# RMII_Ethernet.net
KiCad netlist of a schematic drawn in Altium Designer
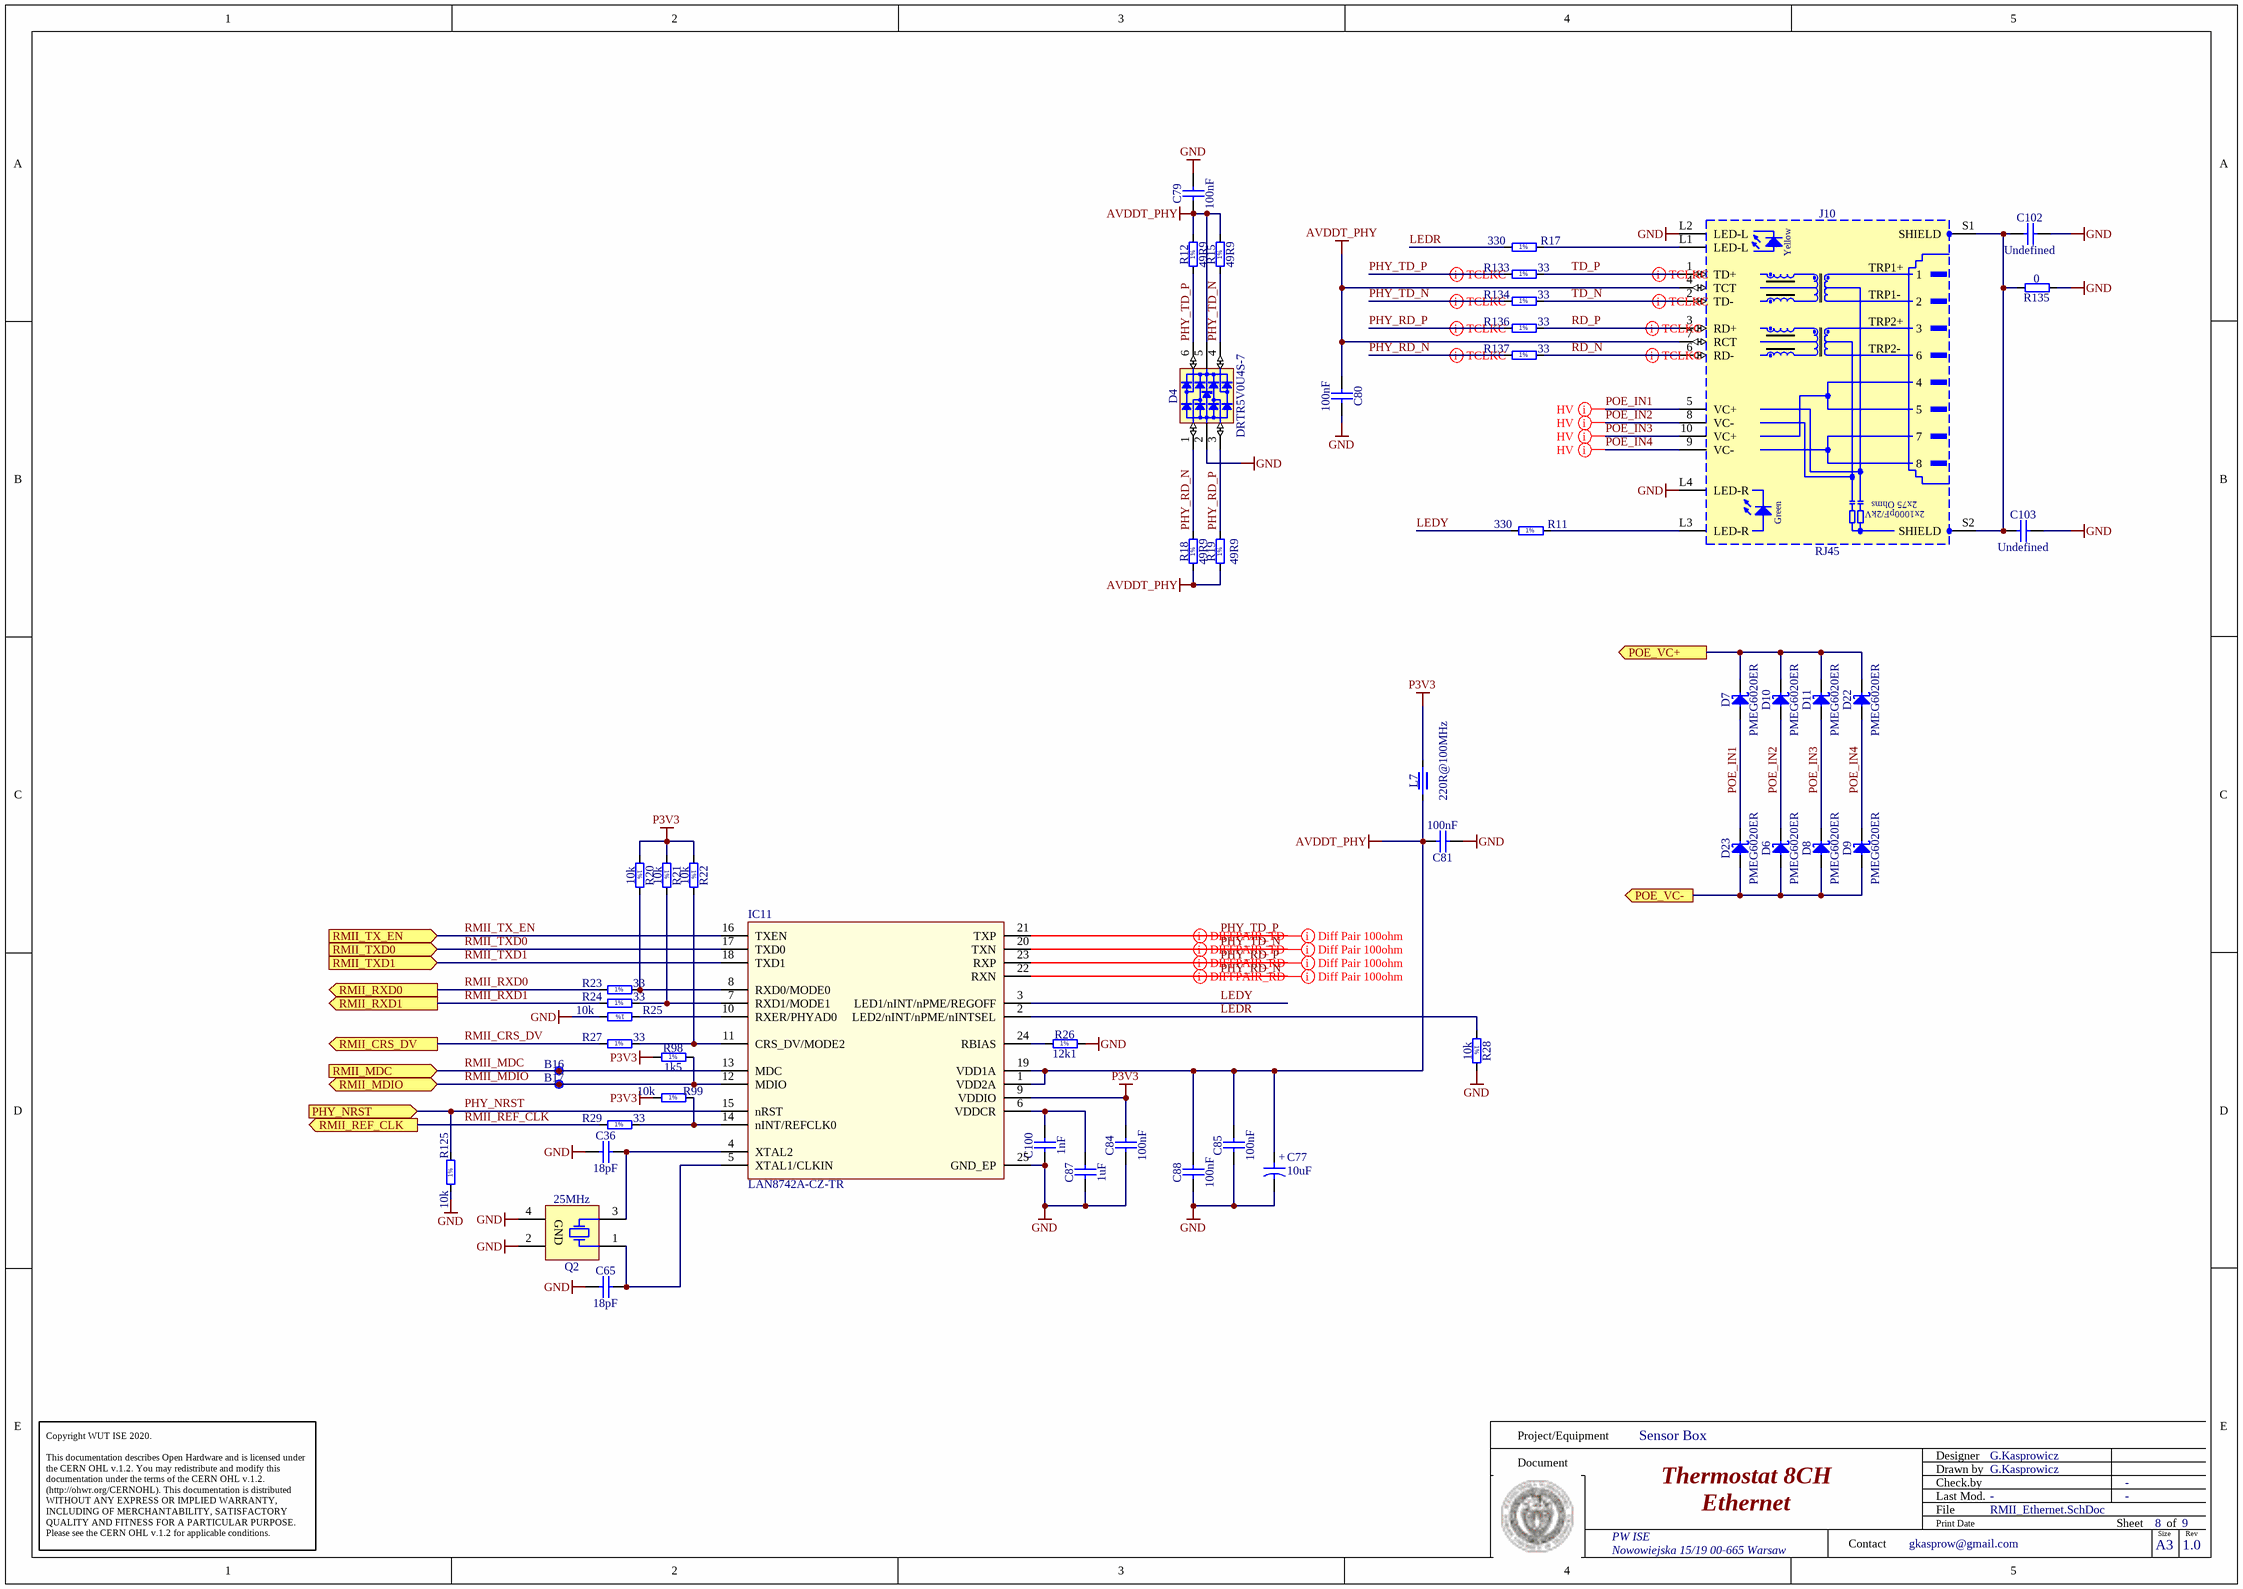
[diagram p0: RMII_Ethernet.SchDoc]

(export (version "E")
  (design (tool "Eeschema 10.0.6"))
  (components
    (comp (ref "B16")
      (value "SMD Pad")
      (footprint "C100")
      (description "Through Hole Pad")
      (fields (field (name "PART NUMBER") "SMD_PAD_D1MM") (field (name "AUTHOR") "CERN DEM JLC"))
      (libsource (lib "Eletro-mechanical") (part "Single SMD Pad (Round)"))
    )
    (comp (ref "B17")
      (value "SMD Pad")
      (footprint "C100")
      (description "Through Hole Pad")
      (fields (field (name "PART NUMBER") "SMD_PAD_D1MM") (field (name "AUTHOR") "CERN DEM JLC"))
      (libsource (lib "Eletro-mechanical") (part "Single SMD Pad (Round)"))
    )
    (comp (ref "C36")
      (value "18pF")
      (footprint "CAPC1005X55N")
      (description "Non-polarised capacitor")
      (fields
        (field (name "PART NUMBER") "CC0402_18PF_50V_5%_C0G")
        (field (name "VOLTAGE") "50V")
        (field (name "AUTHOR") "CERN DEM JLC")
      )
      (libsource (lib "Capacitors") (part "Capacitor - non polarized"))
    )
    (comp (ref "C65")
      (value "18pF")
      (footprint "CAPC1005X55N")
      (description "Non-polarised capacitor")
      (fields
        (field (name "PART NUMBER") "CC0402_18PF_50V_5%_C0G")
        (field (name "VOLTAGE") "50V")
        (field (name "AUTHOR") "CERN DEM JLC")
      )
      (libsource (lib "Capacitors") (part "Capacitor - non polarized"))
    )
    (comp (ref "C77")
      (value "10uF")
      (footprint "CAPMP3216X180N")
      (description "Polarised capacitor")
      (fields
        (field (name "PART NUMBER") "CTE3216-18_10UF_16V_20%_AVX_TCJ")
        (field (name "VOLTAGE") "16V")
        (field (name "AUTHOR") "CERN DEM JLC")
      )
      (libsource (lib "Capacitors") (part "Capacitor - polarized"))
    )
    (comp (ref "C79")
      (value "100nF")
      (footprint "CAPC1005X55N")
      (description "Non-polarised capacitor")
      (fields
        (field (name "PART NUMBER") "CC0402_100NF_16V_10%_X5R")
        (field (name "VOLTAGE") "16V")
        (field (name "AUTHOR") "CERN DEM JLC")
      )
      (libsource (lib "Capacitors") (part "Capacitor - non polarized"))
    )
    (comp (ref "C80")
      (value "100nF")
      (footprint "CAPC1005X55N")
      (description "Non-polarised capacitor")
      (fields
        (field (name "PART NUMBER") "CC0402_100NF_16V_10%_X5R")
        (field (name "VOLTAGE") "16V")
        (field (name "AUTHOR") "CERN DEM JLC")
      )
      (libsource (lib "Capacitors") (part "Capacitor - non polarized"))
    )
    (comp (ref "C81")
      (value "100nF")
      (footprint "CAPC1005X55N")
      (description "Non-polarised capacitor")
      (fields
        (field (name "PART NUMBER") "CC0402_100NF_16V_10%_X5R")
        (field (name "VOLTAGE") "16V")
        (field (name "AUTHOR") "CERN DEM JLC")
      )
      (libsource (lib "Capacitors") (part "Capacitor - non polarized"))
    )
    (comp (ref "C84")
      (value "100nF")
      (footprint "CAPC1005X55N")
      (description "Non-polarised capacitor")
      (fields
        (field (name "PART NUMBER") "CC0402_100NF_16V_10%_X5R")
        (field (name "VOLTAGE") "16V")
        (field (name "AUTHOR") "CERN DEM JLC")
      )
      (libsource (lib "Capacitors") (part "Capacitor - non polarized"))
    )
    (comp (ref "C85")
      (value "100nF")
      (footprint "CAPC1005X55N")
      (description "Non-polarised capacitor")
      (fields
        (field (name "PART NUMBER") "CC0402_100NF_16V_10%_X5R")
        (field (name "VOLTAGE") "16V")
        (field (name "AUTHOR") "CERN DEM JLC")
      )
      (libsource (lib "Capacitors") (part "Capacitor - non polarized"))
    )
    (comp (ref "C87")
      (value "1uF")
      (footprint "CAPC1608X87N")
      (description "Non-polarised capacitor")
      (fields
        (field (name "PART NUMBER") "CC0603_1UF_16V_10%_X7R")
        (field (name "VOLTAGE") "16V")
        (field (name "AUTHOR") "CERN DEM JLC")
      )
      (libsource (lib "Capacitors") (part "Capacitor - non polarized"))
    )
    (comp (ref "C88")
      (value "100nF")
      (footprint "CAPC1005X55N")
      (description "Non-polarised capacitor")
      (fields
        (field (name "PART NUMBER") "CC0402_100NF_16V_10%_X5R")
        (field (name "VOLTAGE") "16V")
        (field (name "AUTHOR") "CERN DEM JLC")
      )
      (libsource (lib "Capacitors") (part "Capacitor - non polarized"))
    )
    (comp (ref "C100")
      (value "1nF")
      (footprint "CAPC1005X55N")
      (description "Non-polarised capacitor")
      (fields
        (field (name "PART NUMBER") "CC0402_1NF_50V_10%_X7R")
        (field (name "VOLTAGE") "50V")
        (field (name "AUTHOR") "CERN DEM JLC")
      )
      (libsource (lib "Capacitors") (part "Capacitor - non polarized"))
    )
    (comp (ref "C102")
      (value "Undefined")
      (footprint "CAPC2012X135N")
      (description "Non-polarised capacitor")
      (fields (field (name "PART NUMBER") "CC0805_NO-VALUE") (field (name "AUTHOR") "CERN DEM JLC"))
      (libsource (lib "Capacitors") (part "Capacitor - non polarized"))
    )
    (comp (ref "C103")
      (value "Undefined")
      (footprint "CAPC2012X135N")
      (description "Non-polarised capacitor")
      (fields (field (name "PART NUMBER") "CC0805_NO-VALUE") (field (name "AUTHOR") "CERN DEM JLC"))
      (libsource (lib "Capacitors") (part "Capacitor - non polarized"))
    )
    (comp (ref "D4")
      (value "DRTR5V0U4S-7")
      (footprint "SOT65P210X110-6N")
      (description "Integrated Quad Ultra-Low Capacitance ESD Protection")
      (fields (field (name "MANUFACTURER") "DIODES") (field (name "AUTHOR") "GK"))
      (libsource (lib "Diodes") (part "D_TVS_DRTR5V0U4S-7"))
    )
    (comp (ref "D6")
      (value "PMEG6020ER")
      (footprint "SODFL3517X110N")
      (description "Schottky Diode")
      (fields
        (field (name "VOLTAGE") "60V")
        (field (name "POWER") "2A")
        (field (name "AUTHOR") "CERN DEM JMW")
      )
      (libsource (lib "ICs And Semiconductors") (part "Diode Schottky"))
    )
    (comp (ref "D7")
      (value "PMEG6020ER")
      (footprint "SODFL3517X110N")
      (description "Schottky Diode")
      (fields
        (field (name "VOLTAGE") "60V")
        (field (name "POWER") "2A")
        (field (name "AUTHOR") "CERN DEM JMW")
      )
      (libsource (lib "ICs And Semiconductors") (part "Diode Schottky"))
    )
    (comp (ref "D8")
      (value "PMEG6020ER")
      (footprint "SODFL3517X110N")
      (description "Schottky Diode")
      (fields
        (field (name "VOLTAGE") "60V")
        (field (name "POWER") "2A")
        (field (name "AUTHOR") "CERN DEM JMW")
      )
      (libsource (lib "ICs And Semiconductors") (part "Diode Schottky"))
    )
    (comp (ref "D9")
      (value "PMEG6020ER")
      (footprint "SODFL3517X110N")
      (description "Schottky Diode")
      (fields
        (field (name "VOLTAGE") "60V")
        (field (name "POWER") "2A")
        (field (name "AUTHOR") "CERN DEM JMW")
      )
      (libsource (lib "ICs And Semiconductors") (part "Diode Schottky"))
    )
    (comp (ref "D10")
      (value "PMEG6020ER")
      (footprint "SODFL3517X110N")
      (description "Schottky Diode")
      (fields
        (field (name "VOLTAGE") "60V")
        (field (name "POWER") "2A")
        (field (name "AUTHOR") "CERN DEM JMW")
      )
      (libsource (lib "ICs And Semiconductors") (part "Diode Schottky"))
    )
    (comp (ref "D11")
      (value "PMEG6020ER")
      (footprint "SODFL3517X110N")
      (description "Schottky Diode")
      (fields
        (field (name "VOLTAGE") "60V")
        (field (name "POWER") "2A")
        (field (name "AUTHOR") "CERN DEM JMW")
      )
      (libsource (lib "ICs And Semiconductors") (part "Diode Schottky"))
    )
    (comp (ref "D22")
      (value "PMEG6020ER")
      (footprint "SODFL3517X110N")
      (description "Schottky Diode")
      (fields
        (field (name "VOLTAGE") "60V")
        (field (name "POWER") "2A")
        (field (name "AUTHOR") "CERN DEM JMW")
      )
      (libsource (lib "ICs And Semiconductors") (part "Diode Schottky"))
    )
    (comp (ref "D23")
      (value "PMEG6020ER")
      (footprint "SODFL3517X110N")
      (description "Schottky Diode")
      (fields
        (field (name "VOLTAGE") "60V")
        (field (name "POWER") "2A")
        (field (name "AUTHOR") "CERN DEM JMW")
      )
      (libsource (lib "ICs And Semiconductors") (part "Diode Schottky"))
    )
    (comp (ref "IC11")
      (value "LAN8742A-CZ-TR")
      (footprint "QFN24_0R5_4X4")
      (libsource (lib "LIBRARY_SCH") (part "IFC_LAN8742A"))
    )
    (comp (ref "J10")
      (value "RJ45")
      (footprint "ABRACON_ARJM11C7-114-BA-EW2")
      (description "MagJack 10/100BaseT, PoE+, 1X1, OG/Y, -40 to 85*C, Tab Up, RoHS")
      (fields
        (field (name "PART NUMBER") "5-2337992-3")
        (field (name "MANUFACTURER") "TE")
        (field (name "AUTHOR") "GK")
      )
      (libsource (lib "LIBRARY_SCH") (part "CON_ETH_POE_ARJM11C7"))
    )
    (comp (ref "L7")
      (value "220R@100MHz")
      (footprint "INDC1005X55N")
      (fields
        (field (name "PART NUMBER") "IND0402_MURATA_BLM15HB221SN1")
        (field (name "POWER") "250mA")
        (field (name "TOLERANCE") "±25%")
        (field (name "AUTHOR") "CERN DEM JLC")
      )
      (libsource (lib "Inductors & Transformers") (part "Ferrite Bead"))
    )
    (comp (ref "Q2")
      (value "25MHz")
      (footprint "XTAL_EPSON_TSX-3225")
      (description "Crystal 4 pins 1=XTAL Control 2=GND3=XTAL 4=GND")
      (fields
        (field (name "PART NUMBER") "XTAL_25MHZ_EPSON_TSX-3225 25.0000MF10Z-AC")
        (field (name "MANUFACTURER") "EPSON")
        (field (name "AUTHOR") "CERN DEM JLC")
      )
      (libsource (lib "ICs And Semiconductors") (part "Quartz Crystal 1X 2GND 3X 4GND"))
    )
    (comp (ref "R11")
      (value "330")
      (footprint "RESC1005X40N")
      (description "Resistor - 1%")
      (fields
        (field (name "PART NUMBER") "R0402_330R_1%_0.0625W_100PPM")
        (field (name "POWER") "0.0625W")
        (field (name "AUTHOR") "CERN DEM JLC")
      )
      (libsource (lib "Resistors") (part "Resistor - 1%"))
    )
    (comp (ref "R12")
      (value "49R9")
      (footprint "RESC1005X40N")
      (description "Resistor - 1%")
      (fields
        (field (name "PART NUMBER") "R0402_49R9_1%_0.0625W_100PPM")
        (field (name "POWER") "0.0625W")
        (field (name "AUTHOR") "CERN DEM JLC")
      )
      (libsource (lib "Resistors") (part "Resistor - 1%"))
    )
    (comp (ref "R15")
      (value "49R9")
      (footprint "RESC1005X40N")
      (description "Resistor - 1%")
      (fields
        (field (name "PART NUMBER") "R0402_49R9_1%_0.0625W_100PPM")
        (field (name "POWER") "0.0625W")
        (field (name "AUTHOR") "CERN DEM JLC")
      )
      (libsource (lib "Resistors") (part "Resistor - 1%"))
    )
    (comp (ref "R17")
      (value "330")
      (footprint "RESC1005X40N")
      (description "Resistor - 1%")
      (fields
        (field (name "PART NUMBER") "R0402_330R_1%_0.0625W_100PPM")
        (field (name "POWER") "0.0625W")
        (field (name "AUTHOR") "CERN DEM JLC")
      )
      (libsource (lib "Resistors") (part "Resistor - 1%"))
    )
    (comp (ref "R18")
      (value "49R9")
      (footprint "RESC1005X40N")
      (description "Resistor - 1%")
      (fields
        (field (name "PART NUMBER") "R0402_49R9_1%_0.0625W_100PPM")
        (field (name "POWER") "0.0625W")
        (field (name "AUTHOR") "CERN DEM JLC")
      )
      (libsource (lib "Resistors") (part "Resistor - 1%"))
    )
    (comp (ref "R19")
      (value "49R9")
      (footprint "RESC1005X40N")
      (description "Resistor - 1%")
      (fields
        (field (name "PART NUMBER") "R0402_49R9_1%_0.0625W_100PPM")
        (field (name "POWER") "0.0625W")
        (field (name "AUTHOR") "CERN DEM JLC")
      )
      (libsource (lib "Resistors") (part "Resistor - 1%"))
    )
    (comp (ref "R20")
      (value "10k")
      (footprint "RESC1005X40N")
      (description "Resistor - 1%")
      (fields
        (field (name "PART NUMBER") "R0402_10K_1%_0.0625W_100PPM")
        (field (name "POWER") "0.0625W")
        (field (name "AUTHOR") "CERN DEM JLC")
      )
      (libsource (lib "Resistors") (part "Resistor - 1%"))
    )
    (comp (ref "R21")
      (value "10k")
      (footprint "RESC1005X40N")
      (description "Resistor - 1%")
      (fields
        (field (name "PART NUMBER") "R0402_10K_1%_0.0625W_100PPM")
        (field (name "POWER") "0.0625W")
        (field (name "AUTHOR") "CERN DEM JLC")
      )
      (libsource (lib "Resistors") (part "Resistor - 1%"))
    )
    (comp (ref "R22")
      (value "10k")
      (footprint "RESC1005X40N")
      (description "Resistor - 1%")
      (fields
        (field (name "PART NUMBER") "R0402_10K_1%_0.0625W_100PPM")
        (field (name "POWER") "0.0625W")
        (field (name "AUTHOR") "CERN DEM JLC")
      )
      (libsource (lib "Resistors") (part "Resistor - 1%"))
    )
    (comp (ref "R23")
      (value "33")
      (footprint "RESC1005X40N")
      (description "Resistor - 1%")
      (fields
        (field (name "PART NUMBER") "R0402_33R_1%_0.0625W_100PPM")
        (field (name "POWER") "0.0625W")
        (field (name "AUTHOR") "CERN DEM JLC")
      )
      (libsource (lib "Resistors") (part "Resistor - 1%"))
    )
    (comp (ref "R24")
      (value "33")
      (footprint "RESC1005X40N")
      (description "Resistor - 1%")
      (fields
        (field (name "PART NUMBER") "R0402_33R_1%_0.0625W_100PPM")
        (field (name "POWER") "0.0625W")
        (field (name "AUTHOR") "CERN DEM JLC")
      )
      (libsource (lib "Resistors") (part "Resistor - 1%"))
    )
    (comp (ref "R25")
      (value "10k")
      (footprint "RESC1005X40N")
      (description "Resistor - 1%")
      (fields
        (field (name "PART NUMBER") "R0402_10K_1%_0.0625W_100PPM")
        (field (name "POWER") "0.0625W")
        (field (name "AUTHOR") "CERN DEM JLC")
      )
      (libsource (lib "Resistors") (part "Resistor - 1%"))
    )
    (comp (ref "R26")
      (value "12k1")
      (footprint "RESC1005X40N")
      (description "Resistor - 1%")
      (fields
        (field (name "PART NUMBER") "R0402_12K1_1%_0.0625W_100PPM")
        (field (name "POWER") "0.0625W")
        (field (name "AUTHOR") "CERN DEM JLC")
      )
      (libsource (lib "Resistors") (part "Resistor - 1%"))
    )
    (comp (ref "R27")
      (value "33")
      (footprint "RESC1005X40N")
      (description "Resistor - 1%")
      (fields
        (field (name "PART NUMBER") "R0402_33R_1%_0.0625W_100PPM")
        (field (name "POWER") "0.0625W")
        (field (name "AUTHOR") "CERN DEM JLC")
      )
      (libsource (lib "Resistors") (part "Resistor - 1%"))
    )
    (comp (ref "R28")
      (value "10k")
      (footprint "RESC1005X40N")
      (description "Resistor - 1%")
      (fields
        (field (name "PART NUMBER") "R0402_10K_1%_0.0625W_100PPM")
        (field (name "POWER") "0.0625W")
        (field (name "AUTHOR") "CERN DEM JLC")
      )
      (libsource (lib "Resistors") (part "Resistor - 1%"))
    )
    (comp (ref "R29")
      (value "33")
      (footprint "RESC1005X40N")
      (description "Resistor - 1%")
      (fields
        (field (name "PART NUMBER") "R0402_33R_1%_0.0625W_100PPM")
        (field (name "POWER") "0.0625W")
        (field (name "AUTHOR") "CERN DEM JLC")
      )
      (libsource (lib "Resistors") (part "Resistor - 1%"))
    )
    (comp (ref "R98")
      (value "1k5")
      (footprint "RESC1005X40N")
      (description "Resistor - 1%")
      (fields
        (field (name "PART NUMBER") "R0402_1K5_1%_0.0625W_100PPM")
        (field (name "POWER") "0.0625W")
        (field (name "AUTHOR") "CERN DEM JLC")
      )
      (libsource (lib "Resistors") (part "Resistor - 1%"))
    )
    (comp (ref "R99")
      (value "10k")
      (footprint "RESC1005X40N")
      (description "Resistor - 1%")
      (fields
        (field (name "PART NUMBER") "R0402_10K_1%_0.0625W_100PPM")
        (field (name "POWER") "0.0625W")
        (field (name "AUTHOR") "CERN DEM JLC")
      )
      (libsource (lib "Resistors") (part "Resistor - 1%"))
    )
    (comp (ref "R125")
      (value "10k")
      (footprint "RESC1005X40N")
      (description "Resistor - 1%")
      (fields
        (field (name "PART NUMBER") "R0402_10K_1%_0.0625W_100PPM")
        (field (name "POWER") "0.0625W")
        (field (name "AUTHOR") "CERN DEM JLC")
      )
      (libsource (lib "Resistors") (part "Resistor - 1%"))
    )
    (comp (ref "R133")
      (value "33")
      (footprint "RESC1005X40N")
      (description "Resistor - 1%")
      (fields
        (field (name "PART NUMBER") "R0402_33R_1%_0.0625W_100PPM")
        (field (name "POWER") "0.0625W")
        (field (name "AUTHOR") "CERN DEM JLC")
      )
      (libsource (lib "Resistors") (part "Resistor - 1%"))
    )
    (comp (ref "R134")
      (value "33")
      (footprint "RESC1005X40N")
      (description "Resistor - 1%")
      (fields
        (field (name "PART NUMBER") "R0402_33R_1%_0.0625W_100PPM")
        (field (name "POWER") "0.0625W")
        (field (name "AUTHOR") "CERN DEM JLC")
      )
      (libsource (lib "Resistors") (part "Resistor - 1%"))
    )
    (comp (ref "R135")
      (value "0")
      (footprint "RESC1608X55N")
      (description "Resistor")
      (fields
        (field (name "PART NUMBER") "R0603_0R_JUMPER")
        (field (name "MANUFACTURER") "GENERIC")
        (field (name "AUTHOR") "CERN DEM JLC")
      )
      (libsource (lib "Resistors") (part "Resistor"))
    )
    (comp (ref "R136")
      (value "33")
      (footprint "RESC1005X40N")
      (description "Resistor - 1%")
      (fields
        (field (name "PART NUMBER") "R0402_33R_1%_0.0625W_100PPM")
        (field (name "POWER") "0.0625W")
        (field (name "AUTHOR") "CERN DEM JLC")
      )
      (libsource (lib "Resistors") (part "Resistor - 1%"))
    )
    (comp (ref "R137")
      (value "33")
      (footprint "RESC1005X40N")
      (description "Resistor - 1%")
      (fields
        (field (name "PART NUMBER") "R0402_33R_1%_0.0625W_100PPM")
        (field (name "POWER") "0.0625W")
        (field (name "AUTHOR") "CERN DEM JLC")
      )
      (libsource (lib "Resistors") (part "Resistor - 1%"))
    )
  )
  (nets
    (net (code "1") (name "/LEDR") (class "Default")
      (node (ref "IC11") (pin "2") (pinfunction "LED2/nINT/nPME/nINTSEL_2") (pintype "passive"))
      (node (ref "R17") (pin "1") (pinfunction "1_1") (pintype "passive"))
      (node (ref "R28") (pin "1") (pinfunction "1_1") (pintype "passive"))
    )
    (net (code "2") (name "/LEDY") (class "Default")
      (node (ref "IC11") (pin "3") (pinfunction "LED1/nINT/nPME/REGOFF_3") (pintype "passive"))
      (node (ref "R11") (pin "1") (pinfunction "1_1") (pintype "passive"))
    )
    (net (code "3") (name "/PHY_NRST") (class "Default")
      (node (ref "IC11") (pin "15") (pinfunction "nRST_15") (pintype "passive"))
      (node (ref "R125") (pin "2") (pinfunction "2_2") (pintype "passive"))
    )
    (net (code "4") (name "/PHY_RD_N") (class "Default")
      (node (ref "D4") (pin "1") (pinfunction "I/O1_1") (pintype "bidirectional"))
      (node (ref "IC11") (pin "22") (pinfunction "RXN_22") (pintype "passive"))
      (node (ref "R137") (pin "1") (pinfunction "1_1") (pintype "passive"))
      (node (ref "R18") (pin "2") (pinfunction "2_2") (pintype "passive"))
    )
    (net (code "5") (name "/PHY_RD_P") (class "Default")
      (node (ref "D4") (pin "3") (pinfunction "I/O2_3") (pintype "bidirectional"))
      (node (ref "IC11") (pin "23") (pinfunction "RXP_23") (pintype "passive"))
      (node (ref "R136") (pin "1") (pinfunction "1_1") (pintype "passive"))
      (node (ref "R19") (pin "2") (pinfunction "2_2") (pintype "passive"))
    )
    (net (code "6") (name "/PHY_TD_N") (class "Default")
      (node (ref "D4") (pin "4") (pinfunction "I/O3_4") (pintype "bidirectional"))
      (node (ref "IC11") (pin "20") (pinfunction "TXN_20") (pintype "passive"))
      (node (ref "R134") (pin "1") (pinfunction "1_1") (pintype "passive"))
      (node (ref "R15") (pin "1") (pinfunction "1_1") (pintype "passive"))
    )
    (net (code "7") (name "/PHY_TD_P") (class "Default")
      (node (ref "D4") (pin "6") (pinfunction "I/O4_6") (pintype "bidirectional"))
      (node (ref "IC11") (pin "21") (pinfunction "TXP_21") (pintype "passive"))
      (node (ref "R12") (pin "1") (pinfunction "1_1") (pintype "passive"))
      (node (ref "R133") (pin "1") (pinfunction "1_1") (pintype "passive"))
    )
    (net (code "8") (name "/POE_IN1") (class "Default")
      (node (ref "D23") (pin "1") (pinfunction "C_1") (pintype "passive"))
      (node (ref "D7") (pin "2") (pinfunction "A_2") (pintype "passive"))
      (node (ref "J10") (pin "5") (pinfunction "VC+_5") (pintype "passive"))
    )
    (net (code "9") (name "/POE_IN2") (class "Default")
      (node (ref "D10") (pin "2") (pinfunction "A_2") (pintype "passive"))
      (node (ref "D6") (pin "1") (pinfunction "C_1") (pintype "passive"))
      (node (ref "J10") (pin "8") (pinfunction "VC-_8") (pintype "passive"))
    )
    (net (code "10") (name "/POE_IN3") (class "Default")
      (node (ref "D11") (pin "2") (pinfunction "A_2") (pintype "passive"))
      (node (ref "D8") (pin "1") (pinfunction "C_1") (pintype "passive"))
      (node (ref "J10") (pin "10") (pinfunction "VC+_10") (pintype "passive"))
    )
    (net (code "11") (name "/POE_IN4") (class "Default")
      (node (ref "D22") (pin "2") (pinfunction "A_2") (pintype "passive"))
      (node (ref "D9") (pin "1") (pinfunction "C_1") (pintype "passive"))
      (node (ref "J10") (pin "9") (pinfunction "VC-_9") (pintype "passive"))
    )
    (net (code "12") (name "/POE_VC+") (class "Default")
      (node (ref "D10") (pin "1") (pinfunction "C_1") (pintype "passive"))
      (node (ref "D11") (pin "1") (pinfunction "C_1") (pintype "passive"))
      (node (ref "D22") (pin "1") (pinfunction "C_1") (pintype "passive"))
      (node (ref "D7") (pin "1") (pinfunction "C_1") (pintype "passive"))
    )
    (net (code "13") (name "/POE_VC-") (class "Default")
      (node (ref "D23") (pin "2") (pinfunction "A_2") (pintype "passive"))
      (node (ref "D6") (pin "2") (pinfunction "A_2") (pintype "passive"))
      (node (ref "D8") (pin "2") (pinfunction "A_2") (pintype "passive"))
      (node (ref "D9") (pin "2") (pinfunction "A_2") (pintype "passive"))
    )
    (net (code "14") (name "/RD_N") (class "Default")
      (node (ref "J10") (pin "6") (pinfunction "RD-_6") (pintype "bidirectional"))
      (node (ref "R137") (pin "2") (pinfunction "2_2") (pintype "passive"))
    )
    (net (code "15") (name "/RD_P") (class "Default")
      (node (ref "J10") (pin "3") (pinfunction "RD+_3") (pintype "bidirectional"))
      (node (ref "R136") (pin "2") (pinfunction "2_2") (pintype "passive"))
    )
    (net (code "16") (name "/RMII_CRS_DV") (class "Default")
      (node (ref "R27") (pin "1") (pinfunction "1_1") (pintype "passive"))
    )
    (net (code "17") (name "/RMII_MDC") (class "Default")
      (node (ref "B16") (pin "1") (pinfunction "1_1") (pintype "bidirectional"))
      (node (ref "IC11") (pin "13") (pinfunction "MDC_13") (pintype "passive"))
    )
    (net (code "18") (name "/RMII_MDIO") (class "Default")
      (node (ref "B17") (pin "1") (pinfunction "1_1") (pintype "bidirectional"))
      (node (ref "IC11") (pin "12") (pinfunction "MDIO_12") (pintype "passive"))
      (node (ref "R98") (pin "2") (pinfunction "2_2") (pintype "passive"))
    )
    (net (code "19") (name "/RMII_REF_CLK") (class "Default")
      (node (ref "R29") (pin "1") (pinfunction "1_1") (pintype "passive"))
    )
    (net (code "20") (name "/RMII_RXD0") (class "Default")
      (node (ref "R23") (pin "1") (pinfunction "1_1") (pintype "passive"))
    )
    (net (code "21") (name "/RMII_RXD1") (class "Default")
      (node (ref "R24") (pin "1") (pinfunction "1_1") (pintype "passive"))
    )
    (net (code "22") (name "/RMII_TXD0") (class "Default")
      (node (ref "IC11") (pin "17") (pinfunction "TXD0_17") (pintype "passive"))
    )
    (net (code "23") (name "/RMII_TXD1") (class "Default")
      (node (ref "IC11") (pin "18") (pinfunction "TXD1_18") (pintype "passive"))
    )
    (net (code "24") (name "/RMII_TX_EN") (class "Default")
      (node (ref "IC11") (pin "16") (pinfunction "TXEN_16") (pintype "passive"))
    )
    (net (code "25") (name "/TD_N") (class "Default")
      (node (ref "J10") (pin "2") (pinfunction "TD-_2") (pintype "bidirectional"))
      (node (ref "R134") (pin "2") (pinfunction "2_2") (pintype "passive"))
    )
    (net (code "26") (name "/TD_P") (class "Default")
      (node (ref "J10") (pin "1") (pinfunction "TD+_1") (pintype "bidirectional"))
      (node (ref "R133") (pin "2") (pinfunction "2_2") (pintype "passive"))
    )
    (net (code "27") (name "AVDDT_PHY") (class "Default")
      (node (ref "C77") (pin "1") (pinfunction "1_1") (pintype "passive"))
      (node (ref "C79") (pin "1") (pinfunction "1_1") (pintype "passive"))
      (node (ref "C80") (pin "2") (pinfunction "2_2") (pintype "passive"))
      (node (ref "C81") (pin "2") (pinfunction "2_2") (pintype "passive"))
      (node (ref "C85") (pin "2") (pinfunction "2_2") (pintype "passive"))
      (node (ref "C88") (pin "2") (pinfunction "2_2") (pintype "passive"))
      (node (ref "D4") (pin "5") (pinfunction "VBUS_5") (pintype "power_in"))
      (node (ref "IC11") (pin "1") (pinfunction "VDD2A_1") (pintype "passive"))
      (node (ref "IC11") (pin "19") (pinfunction "VDD1A_19") (pintype "passive"))
      (node (ref "J10") (pin "4") (pinfunction "TCT_4") (pintype "bidirectional"))
      (node (ref "J10") (pin "7") (pinfunction "RCT_7") (pintype "bidirectional"))
      (node (ref "L7") (pin "1") (pinfunction "1_1") (pintype "passive"))
      (node (ref "R12") (pin "2") (pinfunction "2_2") (pintype "passive"))
      (node (ref "R15") (pin "2") (pinfunction "2_2") (pintype "passive"))
      (node (ref "R18") (pin "1") (pinfunction "1_1") (pintype "passive"))
      (node (ref "R19") (pin "1") (pinfunction "1_1") (pintype "passive"))
    )
    (net (code "28") (name "GND") (class "Default")
      (node (ref "C100") (pin "1") (pinfunction "1_1") (pintype "passive"))
      (node (ref "C102") (pin "2") (pinfunction "2_2") (pintype "passive"))
      (node (ref "C103") (pin "2") (pinfunction "2_2") (pintype "passive"))
      (node (ref "C36") (pin "1") (pinfunction "1_1") (pintype "passive"))
      (node (ref "C65") (pin "1") (pinfunction "1_1") (pintype "passive"))
      (node (ref "C77") (pin "2") (pinfunction "2_2") (pintype "passive"))
      (node (ref "C79") (pin "2") (pinfunction "2_2") (pintype "passive"))
      (node (ref "C80") (pin "1") (pinfunction "1_1") (pintype "passive"))
      (node (ref "C81") (pin "1") (pinfunction "1_1") (pintype "passive"))
      (node (ref "C84") (pin "1") (pinfunction "1_1") (pintype "passive"))
      (node (ref "C85") (pin "1") (pinfunction "1_1") (pintype "passive"))
      (node (ref "C87") (pin "1") (pinfunction "1_1") (pintype "passive"))
      (node (ref "C88") (pin "1") (pinfunction "1_1") (pintype "passive"))
      (node (ref "D4") (pin "2") (pinfunction "GND_2") (pintype "power_in"))
      (node (ref "IC11") (pin "25") (pinfunction "GND_EP_25") (pintype "passive"))
      (node (ref "J10") (pin "L2") (pinfunction "LED-L_L2") (pintype "passive"))
      (node (ref "J10") (pin "L4") (pinfunction "LED-R_L4") (pintype "passive"))
      (node (ref "Q2") (pin "2") (pinfunction "GND_2") (pintype "power_in"))
      (node (ref "Q2") (pin "4") (pinfunction "GND_4") (pintype "power_in"))
      (node (ref "R125") (pin "1") (pinfunction "1_1") (pintype "passive"))
      (node (ref "R135") (pin "1") (pinfunction "1_1") (pintype "passive"))
      (node (ref "R25") (pin "2") (pinfunction "2_2") (pintype "passive"))
      (node (ref "R26") (pin "2") (pinfunction "2_2") (pintype "passive"))
      (node (ref "R28") (pin "2") (pinfunction "2_2") (pintype "passive"))
    )
    (net (code "29") (name "Net-(C102-Pad1)") (class "Default")
      (node (ref "C102") (pin "1") (pinfunction "1_1") (pintype "passive"))
      (node (ref "C103") (pin "1") (pinfunction "1_1") (pintype "passive"))
      (node (ref "J10") (pin "S1") (pinfunction "SHIELD_S1") (pintype "power_in"))
      (node (ref "J10") (pin "S2") (pinfunction "SHIELD_S2") (pintype "power_in"))
      (node (ref "R135") (pin "2") (pinfunction "2_2") (pintype "passive"))
    )
    (net (code "30") (name "Net-(IC11-CRS_DV{slash}MODE2)") (class "Default")
      (node (ref "IC11") (pin "11") (pinfunction "CRS_DV/MODE2_11") (pintype "passive"))
      (node (ref "R22") (pin "2") (pinfunction "2_2") (pintype "passive"))
      (node (ref "R27") (pin "2") (pinfunction "2_2") (pintype "passive"))
    )
    (net (code "31") (name "Net-(IC11-RBIAS)") (class "Default")
      (node (ref "IC11") (pin "24") (pinfunction "RBIAS_24") (pintype "passive"))
      (node (ref "R26") (pin "1") (pinfunction "1_1") (pintype "passive"))
    )
    (net (code "32") (name "Net-(IC11-RXD0{slash}MODE0)") (class "Default")
      (node (ref "IC11") (pin "8") (pinfunction "RXD0/MODE0_8") (pintype "passive"))
      (node (ref "R20") (pin "2") (pinfunction "2_2") (pintype "passive"))
      (node (ref "R23") (pin "2") (pinfunction "2_2") (pintype "passive"))
    )
    (net (code "33") (name "Net-(IC11-RXD1{slash}MODE1)") (class "Default")
      (node (ref "IC11") (pin "7") (pinfunction "RXD1/MODE1_7") (pintype "passive"))
      (node (ref "R21") (pin "2") (pinfunction "2_2") (pintype "passive"))
      (node (ref "R24") (pin "2") (pinfunction "2_2") (pintype "passive"))
    )
    (net (code "34") (name "Net-(IC11-RXER{slash}PHYAD0)") (class "Default")
      (node (ref "IC11") (pin "10") (pinfunction "RXER/PHYAD0_10") (pintype "passive"))
      (node (ref "R25") (pin "1") (pinfunction "1_1") (pintype "passive"))
    )
    (net (code "35") (name "Net-(IC11-VDDCR)") (class "Default")
      (node (ref "C100") (pin "2") (pinfunction "2_2") (pintype "passive"))
      (node (ref "C87") (pin "2") (pinfunction "2_2") (pintype "passive"))
      (node (ref "IC11") (pin "6") (pinfunction "VDDCR_6") (pintype "passive"))
    )
    (net (code "36") (name "Net-(IC11-XTAL1{slash}CLKIN)") (class "Default")
      (node (ref "C65") (pin "2") (pinfunction "2_2") (pintype "passive"))
      (node (ref "IC11") (pin "5") (pinfunction "XTAL1/CLKIN_5") (pintype "passive"))
      (node (ref "Q2") (pin "1") (pinfunction "X_1") (pintype "passive"))
    )
    (net (code "37") (name "Net-(IC11-XTAL2)") (class "Default")
      (node (ref "C36") (pin "2") (pinfunction "2_2") (pintype "passive"))
      (node (ref "IC11") (pin "4") (pinfunction "XTAL2_4") (pintype "passive"))
      (node (ref "Q2") (pin "3") (pinfunction "X_3") (pintype "passive"))
    )
    (net (code "38") (name "Net-(IC11-nINT{slash}REFCLK0)") (class "Default")
      (node (ref "IC11") (pin "14") (pinfunction "nINT/REFCLK0_14") (pintype "passive"))
      (node (ref "R29") (pin "2") (pinfunction "2_2") (pintype "passive"))
      (node (ref "R99") (pin "2") (pinfunction "2_2") (pintype "passive"))
    )
    (net (code "39") (name "Net-(J10-LED-L-PadL1)") (class "Default")
      (node (ref "J10") (pin "L1") (pinfunction "LED-L_L1") (pintype "passive"))
      (node (ref "R17") (pin "2") (pinfunction "2_2") (pintype "passive"))
    )
    (net (code "40") (name "Net-(J10-LED-R-PadL3)") (class "Default")
      (node (ref "J10") (pin "L3") (pinfunction "LED-R_L3") (pintype "passive"))
      (node (ref "R11") (pin "2") (pinfunction "2_2") (pintype "passive"))
    )
    (net (code "41") (name "P3V3") (class "Default")
      (node (ref "C84") (pin "2") (pinfunction "2_2") (pintype "passive"))
      (node (ref "IC11") (pin "9") (pinfunction "VDDIO_9") (pintype "passive"))
      (node (ref "L7") (pin "2") (pinfunction "2_2") (pintype "passive"))
      (node (ref "R20") (pin "1") (pinfunction "1_1") (pintype "passive"))
      (node (ref "R21") (pin "1") (pinfunction "1_1") (pintype "passive"))
      (node (ref "R22") (pin "1") (pinfunction "1_1") (pintype "passive"))
      (node (ref "R98") (pin "1") (pinfunction "1_1") (pintype "passive"))
      (node (ref "R99") (pin "1") (pinfunction "1_1") (pintype "passive"))
    )
  )
)
